# BMS_CPU.net
KiCad netlist of a schematic drawn in Altium Designer
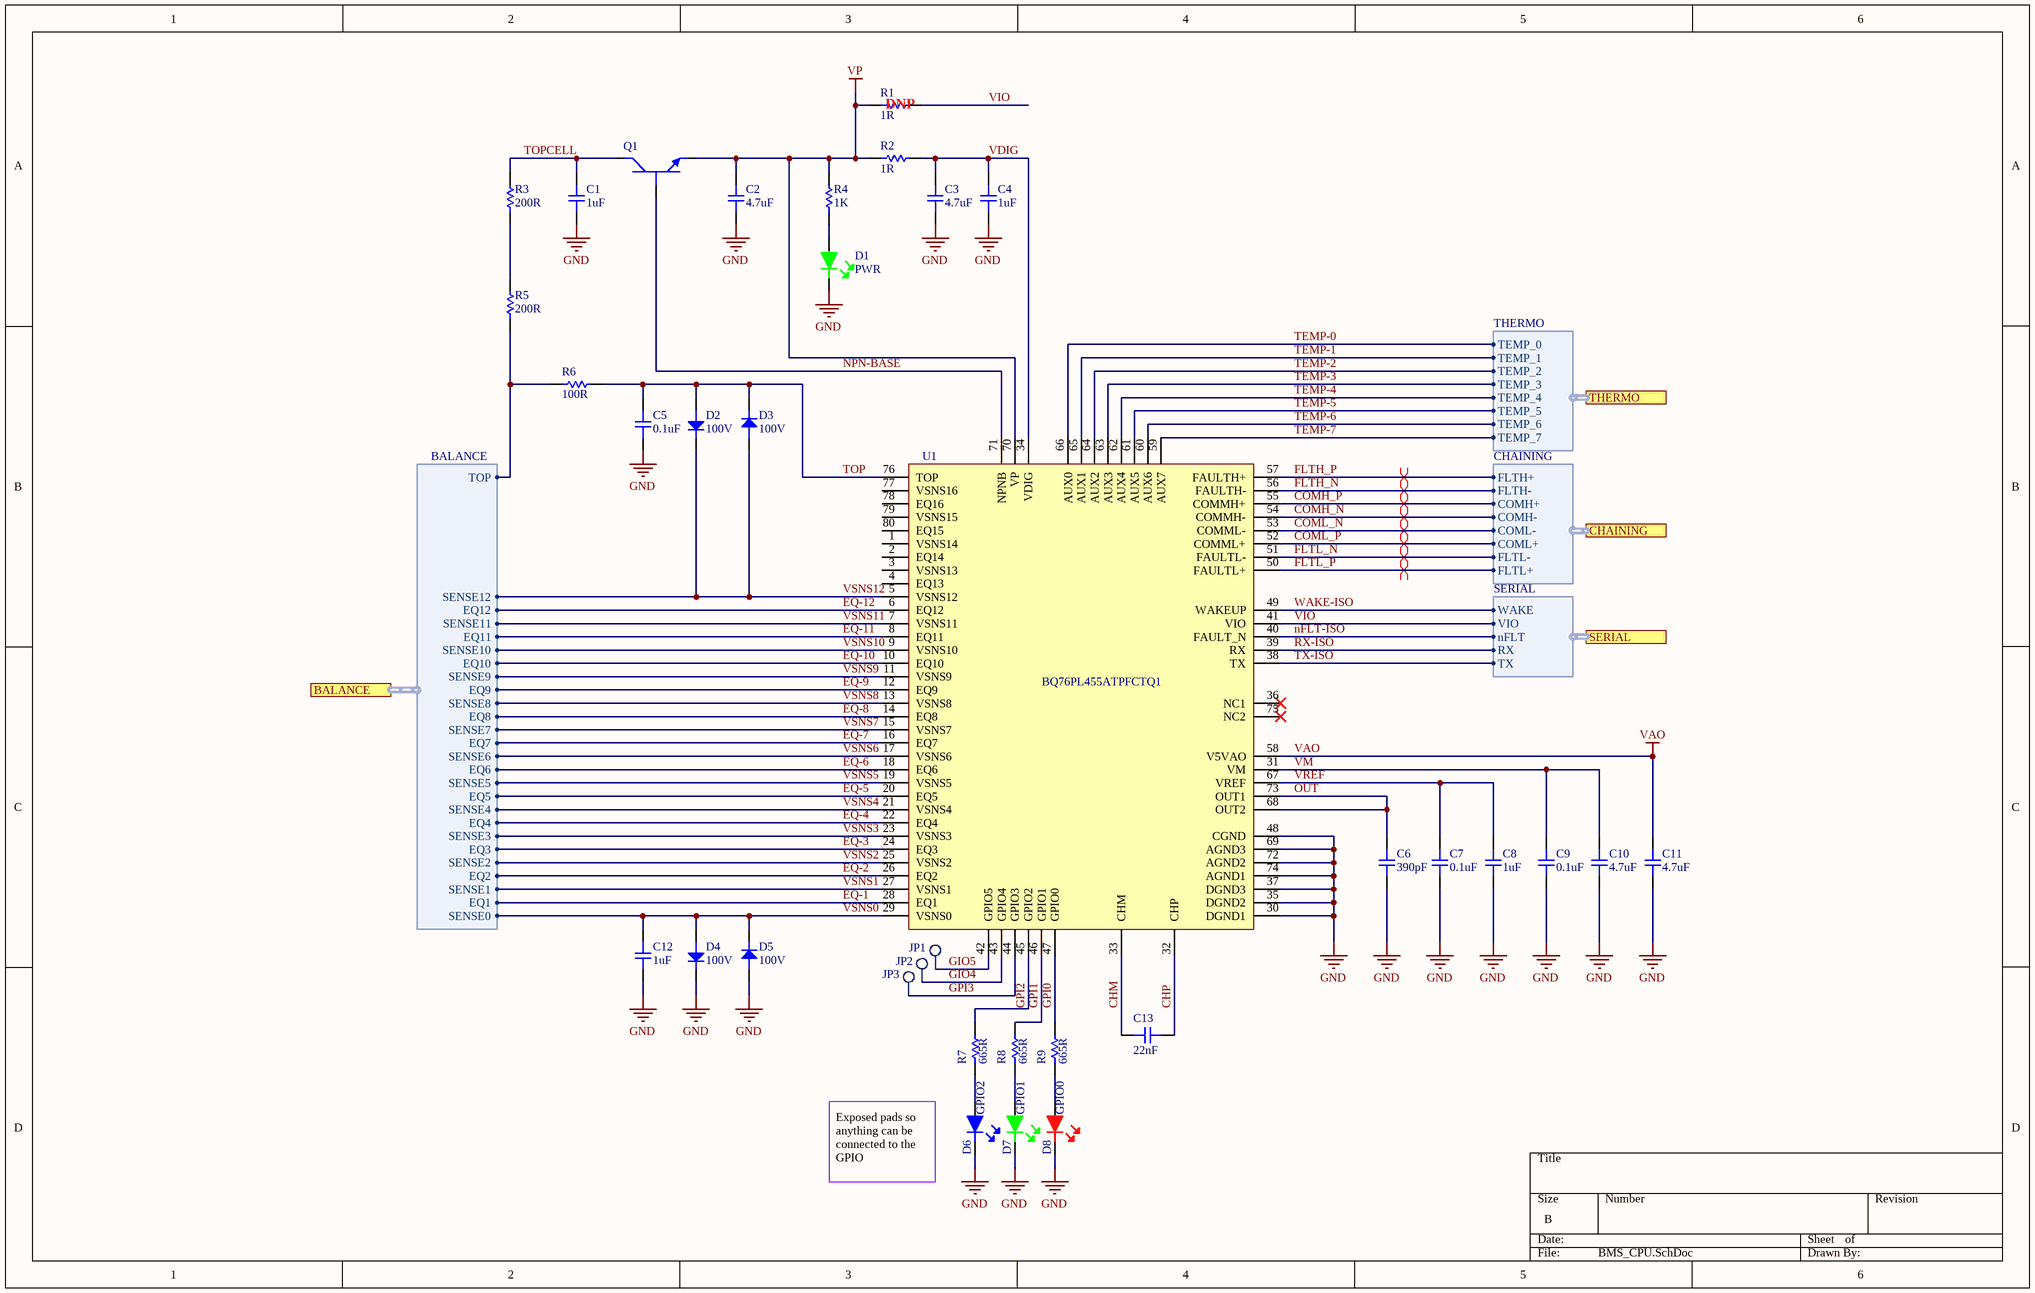
[diagram p0: BMS_CPU.SchDoc]

(export (version "E")
  (design (tool "Eeschema 10.0.6"))
  (components
    (comp (ref "C1")
      (value "1uF")
      (footprint "CAP-0805")
      (description "CAP CER 1UF 50V X5R 0805")
      (fields
        (field (name "MANUFACTURER") "KEMET")
        (field (name "MANUFACTURER PART NUMBER") "C0805C105K5PACTU")
      )
      (libsource (lib "Capacitors") (part "0805-1uF-50V"))
    )
    (comp (ref "C2")
      (value "4.7uF")
      (footprint "CAP-0805")
      (description "CAP CER 4.7UF 16V X5R 0805")
      (fields
        (field (name "MANUFACTURER") "KEMET")
        (field (name "MANUFACTURER PART NUMBER") "C0805C475K4PACTU")
      )
      (libsource (lib "Capacitors") (part "0805-4.7uF-16V"))
    )
    (comp (ref "C3")
      (value "4.7uF")
      (footprint "CAP-0805")
      (description "CAP CER 4.7UF 16V X5R 0805")
      (fields
        (field (name "MANUFACTURER") "KEMET")
        (field (name "MANUFACTURER PART NUMBER") "C0805C475K4PACTU")
      )
      (libsource (lib "Capacitors") (part "0805-4.7uF-16V"))
    )
    (comp (ref "C4")
      (value "1uF")
      (footprint "CAP-0805")
      (description "CAP CER 1UF 16V Y5V 0805")
      (fields
        (field (name "MANUFACTURER") "KEMET")
        (field (name "MANUFACTURER PART NUMBER") "C0805C105Z4VACTU")
      )
      (libsource (lib "Capacitors") (part "0805-1uF-16V"))
    )
    (comp (ref "C5")
      (value "0.1uF")
      (footprint "CAP-0805")
      (description "CAP CER 0.1UF 50V Y5V 0805")
      (fields
        (field (name "MANUFACTURER") "KEMET")
        (field (name "MANUFACTURER PART NUMBER") "C0805C104Z5VACTU")
      )
      (libsource (lib "Capacitors") (part "0805-0.1uF-50V"))
    )
    (comp (ref "C6")
      (value "390pF")
      (footprint "CAP-0805")
      (description "CAP CER 390PF 50V C0G/NP0 0805")
      (fields
        (field (name "MANUFACTURER") "KEMET")
        (field (name "MANUFACTURER PART NUMBER") "C0805C391J5GACTU")
      )
      (libsource (lib "Capacitors") (part "0805-390pF-50V"))
    )
    (comp (ref "C7")
      (value "0.1uF")
      (footprint "CAP-0805")
      (description "CAP CER 0.1UF 50V Y5V 0805")
      (fields
        (field (name "MANUFACTURER") "KEMET")
        (field (name "MANUFACTURER PART NUMBER") "C0805C104Z5VACTU")
      )
      (libsource (lib "Capacitors") (part "0805-0.1uF-50V"))
    )
    (comp (ref "C8")
      (value "1uF")
      (footprint "CAP-0805")
      (description "CAP CER 1UF 50V X5R 0805")
      (fields
        (field (name "MANUFACTURER") "KEMET")
        (field (name "MANUFACTURER PART NUMBER") "C0805C105K5PACTU")
      )
      (libsource (lib "Capacitors") (part "0805-1uF-50V"))
    )
    (comp (ref "C9")
      (value "0.1uF")
      (footprint "CAP-0805")
      (description "CAP CER 0.1UF 50V Y5V 0805")
      (fields
        (field (name "MANUFACTURER") "KEMET")
        (field (name "MANUFACTURER PART NUMBER") "C0805C104Z5VACTU")
      )
      (libsource (lib "Capacitors") (part "0805-0.1uF-50V"))
    )
    (comp (ref "C10")
      (value "4.7uF")
      (footprint "CAP-0805")
      (description "CAP CER 4.7UF 16V X5R 0805")
      (fields
        (field (name "MANUFACTURER") "KEMET")
        (field (name "MANUFACTURER PART NUMBER") "C0805C475K4PACTU")
      )
      (libsource (lib "Capacitors") (part "0805-4.7uF-16V"))
    )
    (comp (ref "C11")
      (value "4.7uF")
      (footprint "CAP-0805")
      (description "CAP CER 4.7UF 16V X5R 0805")
      (fields
        (field (name "MANUFACTURER") "KEMET")
        (field (name "MANUFACTURER PART NUMBER") "C0805C475K4PACTU")
      )
      (libsource (lib "Capacitors") (part "0805-4.7uF-16V"))
    )
    (comp (ref "C12")
      (value "1uF")
      (footprint "CAP-0805")
      (description "CAP CER 1UF 50V X5R 0805")
      (fields
        (field (name "MANUFACTURER") "KEMET")
        (field (name "MANUFACTURER PART NUMBER") "C0805C105K5PACTU")
      )
      (libsource (lib "Capacitors") (part "0805-1uF-50V"))
    )
    (comp (ref "C13")
      (value "22nF")
      (footprint "CAP-0603")
      (description "CAP CER 0.022UF 100V X7R 0603")
      (fields
        (field (name "MANUFACTURER") "KEMET")
        (field (name "MANUFACTURER PART NUMBER") "C0603C223K1RACTU")
      )
      (libsource (lib "Capacitors") (part "0603-22nF-100V"))
    )
    (comp (ref "D1")
      (value "PWR")
      (footprint "LED-0603")
      (description "LED GREEN CLEAR 0603 SMD")
      (fields
        (field (name "MANUFACTURER") "Wurth Electronics")
        (field (name "MANUFACTURER PART NUMBER") "150060VS75000")
      )
      (libsource (lib "LEDs") (part "LED-Green"))
    )
    (comp (ref "D2")
      (value "100V")
      (footprint "DIODE-SOD123")
      (description "DIODE GEN PURP 100V 300MA SOD123")
      (fields (field (name "MANUFACTURER") "Diodes") (field (name "MANUFACTURER PART NUMBER") "1N4148W-7-F"))
      (libsource (lib "Diodes") (part "Diode-100V-0.3W"))
    )
    (comp (ref "D3")
      (value "100V")
      (footprint "DIODE-SOD123")
      (description "DIODE GEN PURP 100V 300MA SOD123")
      (fields (field (name "MANUFACTURER") "Diodes") (field (name "MANUFACTURER PART NUMBER") "1N4148W-7-F"))
      (libsource (lib "Diodes") (part "Diode-100V-0.3W"))
    )
    (comp (ref "D4")
      (value "100V")
      (footprint "DIODE-SOD123")
      (description "DIODE GEN PURP 100V 300MA SOD123")
      (fields (field (name "MANUFACTURER") "Diodes") (field (name "MANUFACTURER PART NUMBER") "1N4148W-7-F"))
      (libsource (lib "Diodes") (part "Diode-100V-0.3W"))
    )
    (comp (ref "D5")
      (value "100V")
      (footprint "DIODE-SOD123")
      (description "DIODE GEN PURP 100V 300MA SOD123")
      (fields (field (name "MANUFACTURER") "Diodes") (field (name "MANUFACTURER PART NUMBER") "1N4148W-7-F"))
      (libsource (lib "Diodes") (part "Diode-100V-0.3W"))
    )
    (comp (ref "D6")
      (value "GPIO2")
      (footprint "LED-0603")
      (description "LED BLUE CLEAR 0603 SMD")
      (fields
        (field (name "MANUFACTURER") "Wurth Electronics")
        (field (name "MANUFACTURER PART NUMBER") "150060BS75000")
      )
      (libsource (lib "LEDs") (part "LED-Blue"))
    )
    (comp (ref "D7")
      (value "GPIO1")
      (footprint "LED-0603")
      (description "LED GREEN CLEAR 0603 SMD")
      (fields
        (field (name "MANUFACTURER") "Wurth Electronics")
        (field (name "MANUFACTURER PART NUMBER") "150060VS75000")
      )
      (libsource (lib "LEDs") (part "LED-Green"))
    )
    (comp (ref "D8")
      (value "GPIO0")
      (footprint "LED-0603")
      (description "LED RED CLEAR 0603 SMD")
      (fields
        (field (name "MANUFACTURER") "Wurth Electronics")
        (field (name "MANUFACTURER PART NUMBER") "150060RS75000")
      )
      (libsource (lib "LEDs") (part "LED-Red"))
    )
    (comp (ref "JP1")
      (value "Testpoint2")
      (footprint "TP2")
      (description "Single layer pad TP")
      (libsource (lib "Misc") (part "Testpoint2"))
    )
    (comp (ref "JP2")
      (value "Testpoint2")
      (footprint "TP2")
      (description "Single layer pad TP")
      (libsource (lib "Misc") (part "Testpoint2"))
    )
    (comp (ref "JP3")
      (value "Testpoint2")
      (footprint "TP2")
      (description "Single layer pad TP")
      (libsource (lib "Misc") (part "Testpoint2"))
    )
    (comp (ref "Q1")
      (value "ZXTN4004KTCDICT-ND")
      (footprint "DPAK-TO252")
      (description "TRANS NPN 150V 1A TO252")
      (fields (field (name "MANUFACTURER") "Diodes") (field (name "MANUFACTURER PART NUMBER") "ZXTN4004KTC"))
      (libsource (lib "Transistors") (part "NPN-150V-1A"))
    )
    (comp (ref "R1")
      (value "1R")
      (footprint "RES-0603")
      (description "RES SMD 1 OHM 1% 1/10W 0603")
      (fields
        (field (name "MANUFACTURER") "Yageo")
        (field (name "MANUFACTURER PART NUMBER") "RC0603FR-071RL")
      )
      (libsource (lib "Resistors") (part "0603-1R"))
    )
    (comp (ref "R2")
      (value "1R")
      (footprint "RES-0603")
      (description "RES SMD 1 OHM 1% 1/10W 0603")
      (fields
        (field (name "MANUFACTURER") "Yageo")
        (field (name "MANUFACTURER PART NUMBER") "RC0603FR-071RL")
      )
      (libsource (lib "Resistors") (part "0603-1R"))
    )
    (comp (ref "R3")
      (value "200R")
      (footprint "RES-2512")
      (description "RES SMD 200 OHM 1% 1W 2512")
      (fields
        (field (name "MANUFACTURER") "Vishay")
        (field (name "MANUFACTURER PART NUMBER") "CRCW2512200RFKEG")
      )
      (libsource (lib "Resistors") (part "2512-200R"))
    )
    (comp (ref "R4")
      (value "1K")
      (footprint "RES-0603")
      (description "RES SMD 1K OHM 1% 1/10W 0603")
      (fields
        (field (name "MANUFACTURER") "Vishay Dale")
        (field (name "MANUFACTURER PART NUMBER") "CRCW06031K00FKEA")
      )
      (libsource (lib "Resistors") (part "0603-1KR"))
    )
    (comp (ref "R5")
      (value "200R")
      (footprint "RES-2512")
      (description "RES SMD 200 OHM 1% 1W 2512")
      (fields
        (field (name "MANUFACTURER") "Vishay")
        (field (name "MANUFACTURER PART NUMBER") "CRCW2512200RFKEG")
      )
      (libsource (lib "Resistors") (part "2512-200R"))
    )
    (comp (ref "R6")
      (value "100R")
      (footprint "RES-1206")
      (description "RES SMD 100 OHM 1% 1/4W 1206")
      (fields
        (field (name "MANUFACTURER") "Yageo")
        (field (name "MANUFACTURER PART NUMBER") "RC1206FR-07100RL")
      )
      (libsource (lib "Resistors") (part "1206-100R"))
    )
    (comp (ref "R7")
      (value "665R")
      (footprint "RES-0603")
      (description "RES SMD 665 OHM 1% 1/10W 0603")
      (fields
        (field (name "MANUFACTURER") "Yageo")
        (field (name "MANUFACTURER PART NUMBER") "RC0603FR-07665RL")
      )
      (libsource (lib "Resistors") (part "0603-665R"))
    )
    (comp (ref "R8")
      (value "665R")
      (footprint "RES-0603")
      (description "RES SMD 665 OHM 1% 1/10W 0603")
      (fields
        (field (name "MANUFACTURER") "Yageo")
        (field (name "MANUFACTURER PART NUMBER") "RC0603FR-07665RL")
      )
      (libsource (lib "Resistors") (part "0603-665R"))
    )
    (comp (ref "R9")
      (value "665R")
      (footprint "RES-0603")
      (description "RES SMD 665 OHM 1% 1/10W 0603")
      (fields
        (field (name "MANUFACTURER") "Yageo")
        (field (name "MANUFACTURER PART NUMBER") "RC0603FR-07665RL")
      )
      (libsource (lib "Resistors") (part "0603-665R"))
    )
    (comp (ref "U1")
      (value "BQ76PL455ATPFCTQ1")
      (footprint "BQ76PL455A")
      (description "IC BATT MONITOR/PROTECT 80TQFP")
      (fields (field (name "MANUFACTURER") "Texas Instruments"))
      (libsource (lib "ICs") (part "BQ76PL455ATPFCTQ1"))
    )
  )
  (nets
    (net (code "5") (name "/CHM") (class "Default")
      (node (ref "C13") (pin "1") (pinfunction "1_1") (pintype "passive"))
      (node (ref "U1") (pin "33") (pinfunction "CHM_33") (pintype "passive"))
    )
    (net (code "6") (name "/CHP") (class "Default")
      (node (ref "C13") (pin "2") (pinfunction "2_2") (pintype "passive"))
      (node (ref "U1") (pin "32") (pinfunction "CHP_32") (pintype "passive"))
    )
    (net (code "7") (name "/COMH_N") (class "Default")
      (node (ref "U1") (pin "54") (pinfunction "COMMH-_54") (pintype "passive"))
    )
    (net (code "8") (name "/COMH_P") (class "Default")
      (node (ref "U1") (pin "55") (pinfunction "COMMH+_55") (pintype "passive"))
    )
    (net (code "9") (name "/COML_N") (class "Default")
      (node (ref "U1") (pin "53") (pinfunction "COMML-_53") (pintype "passive"))
    )
    (net (code "10") (name "/COML_P") (class "Default")
      (node (ref "U1") (pin "52") (pinfunction "COMML+_52") (pintype "passive"))
    )
    (net (code "11") (name "/EQ-1") (class "Default")
      (node (ref "U1") (pin "28") (pinfunction "EQ1_28") (pintype "passive"))
    )
    (net (code "12") (name "/EQ-2") (class "Default")
      (node (ref "U1") (pin "26") (pinfunction "EQ2_26") (pintype "passive"))
    )
    (net (code "13") (name "/EQ-3") (class "Default")
      (node (ref "U1") (pin "24") (pinfunction "EQ3_24") (pintype "passive"))
    )
    (net (code "14") (name "/EQ-4") (class "Default")
      (node (ref "U1") (pin "22") (pinfunction "EQ4_22") (pintype "passive"))
    )
    (net (code "15") (name "/EQ-5") (class "Default")
      (node (ref "U1") (pin "20") (pinfunction "EQ5_20") (pintype "passive"))
    )
    (net (code "16") (name "/EQ-6") (class "Default")
      (node (ref "U1") (pin "18") (pinfunction "EQ6_18") (pintype "passive"))
    )
    (net (code "17") (name "/EQ-7") (class "Default")
      (node (ref "U1") (pin "16") (pinfunction "EQ7_16") (pintype "passive"))
    )
    (net (code "18") (name "/EQ-8") (class "Default")
      (node (ref "U1") (pin "14") (pinfunction "EQ8_14") (pintype "passive"))
    )
    (net (code "19") (name "/EQ-9") (class "Default")
      (node (ref "U1") (pin "12") (pinfunction "EQ9_12") (pintype "passive"))
    )
    (net (code "20") (name "/EQ-10") (class "Default")
      (node (ref "U1") (pin "10") (pinfunction "EQ10_10") (pintype "passive"))
    )
    (net (code "21") (name "/EQ-11") (class "Default")
      (node (ref "U1") (pin "8") (pinfunction "EQ11_8") (pintype "passive"))
    )
    (net (code "22") (name "/EQ-12") (class "Default")
      (node (ref "U1") (pin "6") (pinfunction "EQ12_6") (pintype "passive"))
    )
    (net (code "23") (name "/FLTH_N") (class "Default")
      (node (ref "U1") (pin "56") (pinfunction "FAULTH-_56") (pintype "passive"))
    )
    (net (code "24") (name "/FLTH_P") (class "Default")
      (node (ref "U1") (pin "57") (pinfunction "FAULTH+_57") (pintype "passive"))
    )
    (net (code "25") (name "/FLTL_N") (class "Default")
      (node (ref "U1") (pin "51") (pinfunction "FAULTL-_51") (pintype "passive"))
    )
    (net (code "26") (name "/FLTL_P") (class "Default")
      (node (ref "U1") (pin "50") (pinfunction "FAULTL+_50") (pintype "passive"))
    )
    (net (code "27") (name "/GIO4") (class "Default")
      (node (ref "JP2") (pin "1") (pinfunction "1_1") (pintype "passive"))
      (node (ref "U1") (pin "43") (pinfunction "GPIO4_43") (pintype "passive"))
    )
    (net (code "28") (name "/GIO5") (class "Default")
      (node (ref "JP1") (pin "1") (pinfunction "1_1") (pintype "passive"))
      (node (ref "U1") (pin "42") (pinfunction "GPIO5_42") (pintype "passive"))
    )
    (net (code "29") (name "/GPI0") (class "Default")
      (node (ref "R9") (pin "2") (pinfunction "2_2") (pintype "passive"))
      (node (ref "U1") (pin "47") (pinfunction "GPIO0_47") (pintype "passive"))
    )
    (net (code "30") (name "/GPI1") (class "Default")
      (node (ref "R8") (pin "2") (pinfunction "2_2") (pintype "passive"))
      (node (ref "U1") (pin "46") (pinfunction "GPIO1_46") (pintype "passive"))
    )
    (net (code "31") (name "/GPI2") (class "Default")
      (node (ref "R7") (pin "2") (pinfunction "2_2") (pintype "passive"))
      (node (ref "U1") (pin "45") (pinfunction "GPIO2_45") (pintype "passive"))
    )
    (net (code "32") (name "/GPI3") (class "Default")
      (node (ref "JP3") (pin "1") (pinfunction "1_1") (pintype "passive"))
      (node (ref "U1") (pin "44") (pinfunction "GPIO3_44") (pintype "passive"))
    )
    (net (code "33") (name "/NPN-BASE") (class "Default")
      (node (ref "Q1") (pin "1") (pinfunction "1_1") (pintype "passive"))
      (node (ref "U1") (pin "71") (pinfunction "NPNB_71") (pintype "passive"))
    )
    (net (code "34") (name "/OUT") (class "Default")
      (node (ref "C6") (pin "2") (pinfunction "2_2") (pintype "passive"))
      (node (ref "U1") (pin "68") (pinfunction "OUT2_68") (pintype "passive"))
      (node (ref "U1") (pin "73") (pinfunction "OUT1_73") (pintype "passive"))
    )
    (net (code "35") (name "/RX-ISO") (class "Default")
      (node (ref "U1") (pin "39") (pinfunction "RX_39") (pintype "passive"))
    )
    (net (code "36") (name "/TEMP-0") (class "Default")
      (node (ref "U1") (pin "66") (pinfunction "AUX0_66") (pintype "passive"))
    )
    (net (code "37") (name "/TEMP-1") (class "Default")
      (node (ref "U1") (pin "65") (pinfunction "AUX1_65") (pintype "passive"))
    )
    (net (code "38") (name "/TEMP-2") (class "Default")
      (node (ref "U1") (pin "64") (pinfunction "AUX2_64") (pintype "passive"))
    )
    (net (code "39") (name "/TEMP-3") (class "Default")
      (node (ref "U1") (pin "63") (pinfunction "AUX3_63") (pintype "passive"))
    )
    (net (code "40") (name "/TEMP-4") (class "Default")
      (node (ref "U1") (pin "62") (pinfunction "AUX4_62") (pintype "passive"))
    )
    (net (code "41") (name "/TEMP-5") (class "Default")
      (node (ref "U1") (pin "61") (pinfunction "AUX5_61") (pintype "passive"))
    )
    (net (code "42") (name "/TEMP-6") (class "Default")
      (node (ref "U1") (pin "60") (pinfunction "AUX6_60") (pintype "passive"))
    )
    (net (code "43") (name "/TEMP-7") (class "Default")
      (node (ref "U1") (pin "59") (pinfunction "AUX7_59") (pintype "passive"))
    )
    (net (code "44") (name "/TOP") (class "Default")
      (node (ref "C5") (pin "1") (pinfunction "1_1") (pintype "passive"))
      (node (ref "D2") (pin "2") (pinfunction "2_2") (pintype "passive"))
      (node (ref "D3") (pin "1") (pinfunction "1_1") (pintype "passive"))
      (node (ref "R6") (pin "2") (pinfunction "2_2") (pintype "passive"))
      (node (ref "U1") (pin "76") (pinfunction "TOP_76") (pintype "passive"))
    )
    (net (code "45") (name "/TOPCELL") (class "Default")
      (node (ref "C1") (pin "2") (pinfunction "2_2") (pintype "passive"))
      (node (ref "Q1") (pin "2") (pinfunction "2_2") (pintype "passive"))
      (node (ref "R3") (pin "2") (pinfunction "2_2") (pintype "passive"))
    )
    (net (code "46") (name "/TX-ISO") (class "Default")
      (node (ref "U1") (pin "38") (pinfunction "TX_38") (pintype "passive"))
    )
    (net (code "47") (name "/VDIG") (class "Default")
      (node (ref "C3") (pin "2") (pinfunction "2_2") (pintype "passive"))
      (node (ref "C4") (pin "2") (pinfunction "2_2") (pintype "passive"))
      (node (ref "R2") (pin "2") (pinfunction "2_2") (pintype "passive"))
      (node (ref "U1") (pin "34") (pinfunction "VDIG_34") (pintype "passive"))
    )
    (net (code "48") (name "/VIO") (class "Default")
      (node (ref "R1") (pin "2") (pinfunction "2_2") (pintype "passive"))
      (node (ref "U1") (pin "41") (pinfunction "VIO_41") (pintype "passive"))
    )
    (net (code "49") (name "/VM") (class "Default")
      (node (ref "C10") (pin "2") (pinfunction "2_2") (pintype "passive"))
      (node (ref "C9") (pin "2") (pinfunction "2_2") (pintype "passive"))
      (node (ref "U1") (pin "31") (pinfunction "VM_31") (pintype "passive"))
    )
    (net (code "50") (name "/VREF") (class "Default")
      (node (ref "C7") (pin "1") (pinfunction "1_1") (pintype "passive"))
      (node (ref "C8") (pin "2") (pinfunction "2_2") (pintype "passive"))
      (node (ref "U1") (pin "67") (pinfunction "VREF_67") (pintype "passive"))
    )
    (net (code "51") (name "/VSNS0") (class "Default")
      (node (ref "C12") (pin "2") (pinfunction "2_2") (pintype "passive"))
      (node (ref "D4") (pin "2") (pinfunction "2_2") (pintype "passive"))
      (node (ref "D5") (pin "1") (pinfunction "1_1") (pintype "passive"))
      (node (ref "U1") (pin "29") (pinfunction "VSNS0_29") (pintype "passive"))
    )
    (net (code "52") (name "/VSNS1") (class "Default")
      (node (ref "U1") (pin "27") (pinfunction "VSNS1_27") (pintype "passive"))
    )
    (net (code "53") (name "/VSNS2") (class "Default")
      (node (ref "U1") (pin "25") (pinfunction "VSNS2_25") (pintype "passive"))
    )
    (net (code "54") (name "/VSNS3") (class "Default")
      (node (ref "U1") (pin "23") (pinfunction "VSNS3_23") (pintype "passive"))
    )
    (net (code "55") (name "/VSNS4") (class "Default")
      (node (ref "U1") (pin "21") (pinfunction "VSNS4_21") (pintype "passive"))
    )
    (net (code "56") (name "/VSNS5") (class "Default")
      (node (ref "U1") (pin "19") (pinfunction "VSNS5_19") (pintype "passive"))
    )
    (net (code "57") (name "/VSNS6") (class "Default")
      (node (ref "U1") (pin "17") (pinfunction "VSNS6_17") (pintype "passive"))
    )
    (net (code "58") (name "/VSNS7") (class "Default")
      (node (ref "U1") (pin "15") (pinfunction "VSNS7_15") (pintype "passive"))
    )
    (net (code "59") (name "/VSNS8") (class "Default")
      (node (ref "U1") (pin "13") (pinfunction "VSNS8_13") (pintype "passive"))
    )
    (net (code "60") (name "/VSNS9") (class "Default")
      (node (ref "U1") (pin "11") (pinfunction "VSNS9_11") (pintype "passive"))
    )
    (net (code "61") (name "/VSNS10") (class "Default")
      (node (ref "U1") (pin "9") (pinfunction "VSNS10_9") (pintype "passive"))
    )
    (net (code "62") (name "/VSNS11") (class "Default")
      (node (ref "U1") (pin "7") (pinfunction "VSNS11_7") (pintype "passive"))
    )
    (net (code "63") (name "/VSNS12") (class "Default")
      (node (ref "D2") (pin "1") (pinfunction "1_1") (pintype "passive"))
      (node (ref "D3") (pin "2") (pinfunction "2_2") (pintype "passive"))
      (node (ref "U1") (pin "5") (pinfunction "VSNS12_5") (pintype "passive"))
    )
    (net (code "64") (name "/WAKE-ISO") (class "Default")
      (node (ref "U1") (pin "49") (pinfunction "WAKEUP_49") (pintype "passive"))
    )
    (net (code "65") (name "/nFLT-ISO") (class "Default")
      (node (ref "U1") (pin "40") (pinfunction "FAULT_N_40") (pintype "passive"))
    )
    (net (code "70") (name "GND") (class "Default")
      (node (ref "C1") (pin "1") (pinfunction "1_1") (pintype "passive"))
      (node (ref "C10") (pin "1") (pinfunction "1_1") (pintype "passive"))
      (node (ref "C11") (pin "1") (pinfunction "1_1") (pintype "passive"))
      (node (ref "C12") (pin "1") (pinfunction "1_1") (pintype "passive"))
      (node (ref "C2") (pin "1") (pinfunction "1_1") (pintype "passive"))
      (node (ref "C3") (pin "1") (pinfunction "1_1") (pintype "passive"))
      (node (ref "C4") (pin "1") (pinfunction "1_1") (pintype "passive"))
      (node (ref "C5") (pin "2") (pinfunction "2_2") (pintype "passive"))
      (node (ref "C6") (pin "1") (pinfunction "1_1") (pintype "passive"))
      (node (ref "C7") (pin "2") (pinfunction "2_2") (pintype "passive"))
      (node (ref "C8") (pin "1") (pinfunction "1_1") (pintype "passive"))
      (node (ref "C9") (pin "1") (pinfunction "1_1") (pintype "passive"))
      (node (ref "D1") (pin "2") (pinfunction "2_2") (pintype "passive"))
      (node (ref "D4") (pin "1") (pinfunction "1_1") (pintype "passive"))
      (node (ref "D5") (pin "2") (pinfunction "2_2") (pintype "passive"))
      (node (ref "D6") (pin "2") (pinfunction "2_2") (pintype "passive"))
      (node (ref "D7") (pin "2") (pinfunction "2_2") (pintype "passive"))
      (node (ref "D8") (pin "2") (pinfunction "2_2") (pintype "passive"))
      (node (ref "U1") (pin "30") (pinfunction "DGND1_30") (pintype "passive"))
      (node (ref "U1") (pin "35") (pinfunction "DGND2_35") (pintype "passive"))
      (node (ref "U1") (pin "37") (pinfunction "DGND3_37") (pintype "passive"))
      (node (ref "U1") (pin "48") (pinfunction "CGND_48") (pintype "passive"))
      (node (ref "U1") (pin "69") (pinfunction "AGND3_69") (pintype "passive"))
      (node (ref "U1") (pin "72") (pinfunction "AGND2_72") (pintype "passive"))
      (node (ref "U1") (pin "74") (pinfunction "AGND1_74") (pintype "passive"))
    )
    (net (code "71") (name "Net-(D1-Pad1)") (class "Default")
      (node (ref "D1") (pin "1") (pinfunction "1_1") (pintype "passive"))
      (node (ref "R4") (pin "1") (pinfunction "1_1") (pintype "passive"))
    )
    (net (code "72") (name "Net-(D6-Pad1)") (class "Default")
      (node (ref "D6") (pin "1") (pinfunction "1_1") (pintype "passive"))
      (node (ref "R7") (pin "1") (pinfunction "1_1") (pintype "passive"))
    )
    (net (code "73") (name "Net-(D7-Pad1)") (class "Default")
      (node (ref "D7") (pin "1") (pinfunction "1_1") (pintype "passive"))
      (node (ref "R8") (pin "1") (pinfunction "1_1") (pintype "passive"))
    )
    (net (code "74") (name "Net-(D8-Pad1)") (class "Default")
      (node (ref "D8") (pin "1") (pinfunction "1_1") (pintype "passive"))
      (node (ref "R9") (pin "1") (pinfunction "1_1") (pintype "passive"))
    )
    (net (code "75") (name "Net-(R3-Pad1)") (class "Default")
      (node (ref "R3") (pin "1") (pinfunction "1_1") (pintype "passive"))
      (node (ref "R5") (pin "2") (pinfunction "2_2") (pintype "passive"))
    )
    (net (code "76") (name "Net-(R5-Pad1)") (class "Default")
      (node (ref "R5") (pin "1") (pinfunction "1_1") (pintype "passive"))
      (node (ref "R6") (pin "1") (pinfunction "1_1") (pintype "passive"))
    )
    (net (code "77") (name "VAO") (class "Default")
      (node (ref "C11") (pin "2") (pinfunction "2_2") (pintype "passive"))
      (node (ref "U1") (pin "58") (pinfunction "V5VAO_58") (pintype "passive"))
    )
    (net (code "78") (name "VP") (class "Default")
      (node (ref "C2") (pin "2") (pinfunction "2_2") (pintype "passive"))
      (node (ref "Q1") (pin "3") (pinfunction "3_3") (pintype "passive"))
      (node (ref "R1") (pin "1") (pinfunction "1_1") (pintype "passive"))
      (node (ref "R2") (pin "1") (pinfunction "1_1") (pintype "passive"))
      (node (ref "R4") (pin "2") (pinfunction "2_2") (pintype "passive"))
      (node (ref "U1") (pin "70") (pinfunction "VP_70") (pintype "passive"))
    )
    (net (code "79") (name "unconnected-(U1-EQ13-Pad4)") (class "Default")
      (node (ref "U1") (pin "4") (pinfunction "EQ13_4") (pintype "passive"))
    )
    (net (code "80") (name "unconnected-(U1-EQ14-Pad2)") (class "Default")
      (node (ref "U1") (pin "2") (pinfunction "EQ14_2") (pintype "passive"))
    )
    (net (code "81") (name "unconnected-(U1-EQ15-Pad80)") (class "Default")
      (node (ref "U1") (pin "80") (pinfunction "EQ15_80") (pintype "passive"))
    )
    (net (code "82") (name "unconnected-(U1-EQ16-Pad78)") (class "Default")
      (node (ref "U1") (pin "78") (pinfunction "EQ16_78") (pintype "passive"))
    )
    (net (code "83") (name "unconnected-(U1-NC1-Pad36)") (class "Default")
      (node (ref "U1") (pin "36") (pinfunction "NC1_36") (pintype "passive+no_connect"))
    )
    (net (code "84") (name "unconnected-(U1-NC2-Pad75)") (class "Default")
      (node (ref "U1") (pin "75") (pinfunction "NC2_75") (pintype "passive+no_connect"))
    )
    (net (code "85") (name "unconnected-(U1-VSNS13-Pad3)") (class "Default")
      (node (ref "U1") (pin "3") (pinfunction "VSNS13_3") (pintype "passive"))
    )
    (net (code "86") (name "unconnected-(U1-VSNS14-Pad1)") (class "Default")
      (node (ref "U1") (pin "1") (pinfunction "VSNS14_1") (pintype "passive"))
    )
    (net (code "87") (name "unconnected-(U1-VSNS15-Pad79)") (class "Default")
      (node (ref "U1") (pin "79") (pinfunction "VSNS15_79") (pintype "passive"))
    )
    (net (code "88") (name "unconnected-(U1-VSNS16-Pad77)") (class "Default")
      (node (ref "U1") (pin "77") (pinfunction "VSNS16_77") (pintype "passive"))
    )
  )
)
